# arduino_sheild_1.net
KiCad netlist of a schematic drawn in Altium Designer
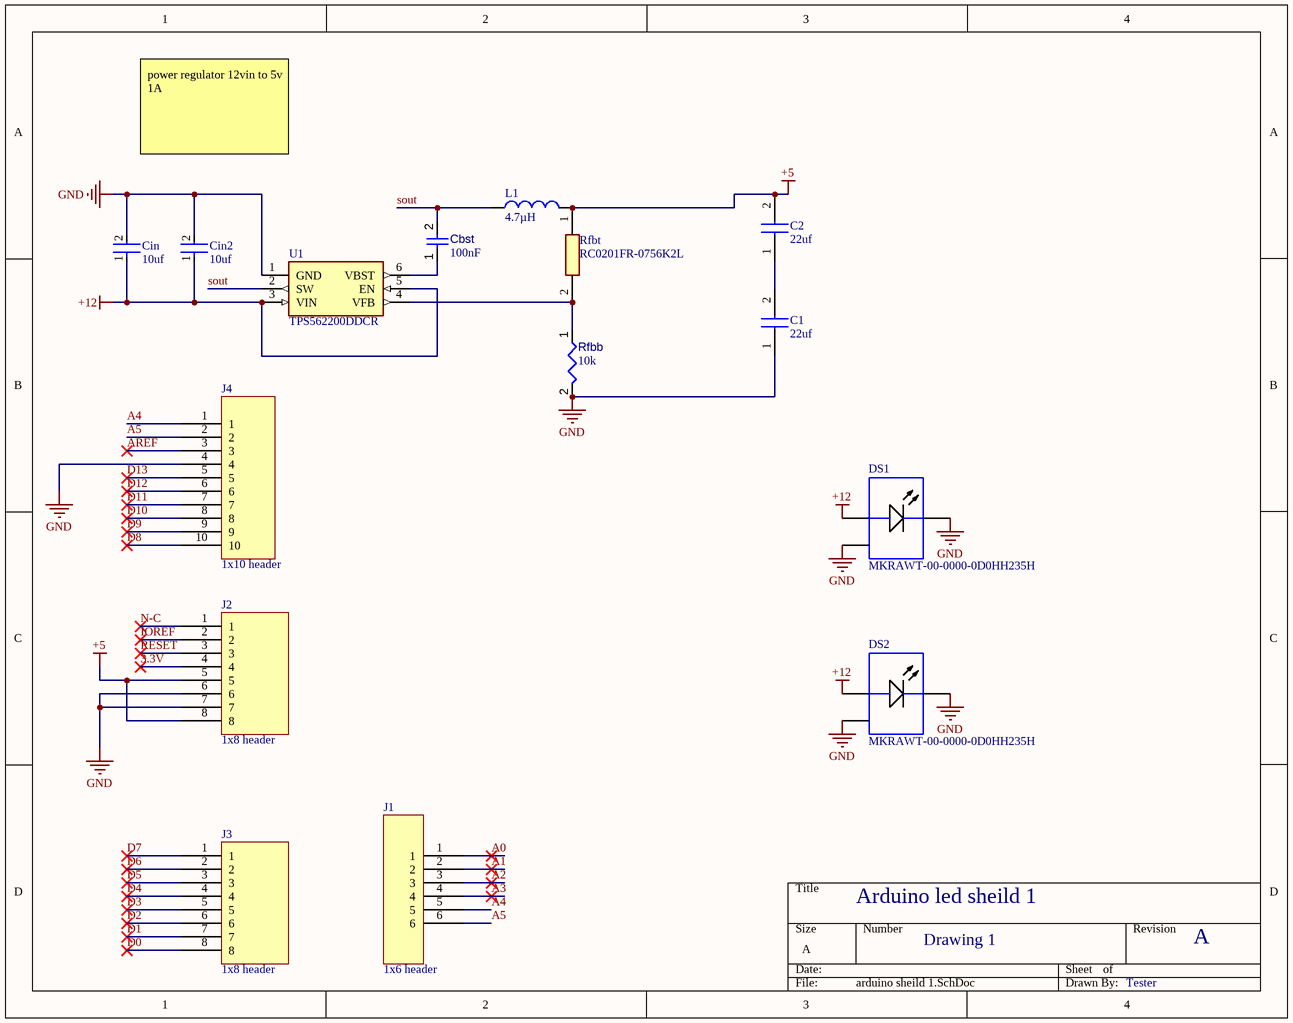
[diagram p0: arduino sheild 1.SchDoc]

(export (version "E")
  (design (tool "Eeschema 10.0.6"))
  (components
    (comp (ref "C1")
      (value "22uf")
      (footprint "SamacSys:CAPC2114X95N")
      (description "Capacitor")
      (fields (field (name "MANUFACTURER_PART_NUMBER") "MSASL219LB5226MTNA01"))
      (libsource (lib "SamacSys") (part "MSASL219LB5226MTNA01"))
    )
    (comp (ref "C2")
      (value "22uf")
      (footprint "SamacSys:CAPC2114X95N")
      (description "Capacitor")
      (fields (field (name "MANUFACTURER_PART_NUMBER") "MSASL219LB5226MTNA01"))
      (libsource (lib "SamacSys") (part "MSASL219LB5226MTNA01"))
    )
    (comp (ref "Cbst")
      (value "100nF")
      (footprint "CAPC2012X75N")
      (description "25V 100nF X7R 卤10% 0805 Multilayer Ceramic Capacitors MLCC - SMD/SMT ROHS")
      (fields (field (name "TOLERANCE") "10%") (field (name "Comment") "08053C104KAT2A"))
      (libsource (lib "Yishak Kalu") (part "CAP-NP-2"))
    )
    (comp (ref "Cin")
      (value "10uf")
      (footprint "FP-GRM21B-0_15-IPC_C")
      (description "Chip Multilayer Ceramic Capacitors for General Purpose, 0805, 10uF, X5R, 15%, 10%, 25V")
      (fields (field (name "VOLTAGE") "25V") (field (name "TOLERANCE") "10%"))
      (libsource (lib "Altium Content Vault") (part "b4654b650e69147ec39a6b967a45e02"))
    )
    (comp (ref "Cin2")
      (value "10uf")
      (footprint "FP-GRM21B-0_15-IPC_C")
      (description "Chip Multilayer Ceramic Capacitors for General Purpose, 0805, 10uF, X5R, 15%, 10%, 25V")
      (fields (field (name "VOLTAGE") "25V") (field (name "TOLERANCE") "10%"))
      (libsource (lib "Altium Content Vault") (part "b4654b650e69147ec39a6b967a45e02"))
    )
    (comp (ref "DS1")
      (value "MKRAWT-00-0000-0D0HH235H")
      (footprint "CREE-MK-R-2_V")
      (description "LED, White, 12 V, 2-Pin SMD, RoHS, Tape and Reel")
      (libsource (lib "Altium Content Vault") (part "LED_WHITE-3"))
    )
    (comp (ref "DS2")
      (value "MKRAWT-00-0000-0D0HH235H")
      (footprint "CREE-MK-R-2_V")
      (description "LED, White, 12 V, 2-Pin SMD, RoHS, Tape and Reel")
      (libsource (lib "Altium Content Vault") (part "LED_WHITE-3"))
    )
    (comp (ref "J1")
      (value "1x6 header")
      (footprint "1x6 header")
      (description "1x6 pin header")
      (libsource (lib "Schlib1") (part "6 pin header"))
    )
    (comp (ref "J2")
      (value "1x8 header")
      (footprint "1x8 header")
      (description "1x8 header pin")
      (libsource (lib "Schlib1") (part "8 pin header"))
    )
    (comp (ref "J3")
      (value "1x8 header")
      (footprint "1x8 header")
      (description "1x8 header pin")
      (libsource (lib "Schlib1") (part "8 pin header"))
    )
    (comp (ref "J4")
      (value "1x10 header")
      (footprint "1x10 pin header")
      (description "1x10 header pin")
      (libsource (lib "Schlib1") (part "10 pin header"))
    )
    (comp (ref "L1")
      (value "4.7µH")
      (footprint "INDP6060X450N")
      (description "Inductor Power Semi-Shielded Wirewound 4.7uH 30% 100KHz 15Q-Factor Ferrite 3A 0.0376Ohm DCR T/R")
      (fields (field (name "TOLERANCE") "30%") (field (name "Comment") "SRN6045-4R7Y"))
      (libsource (lib "Yishak Kalu") (part "IND-2"))
    )
    (comp (ref "Rfbb")
      (value "10k")
      (footprint "RESC0603X26N")
      (description "Res Thick Film 0201 10K Ohm 1% 0.05W(1/20W) ±200ppm/C Pad SMD T/R")
      (fields (field (name "TOLERANCE") "1%") (field (name "Comment") "RC0201FR-0710KL"))
      (libsource (lib "Yishak Kalu") (part "RES-2"))
    )
    (comp (ref "Rfbt")
      (value "RC0201FR-0756K2L")
      (footprint "SamacSys:RESC0603X26N")
      (description "Resistor")
      (fields (field (name "MOUSER PART NUMBER") "603-RC0201FR-0756K2L"))
      (libsource (lib "SamacSys") (part "RC0201FR-0756K2L"))
    )
    (comp (ref "U1")
      (value "TPS562200DDCR")
      (footprint "SamacSys:SOT95P280X110-6N")
      (description "Undefined or Miscellaneous")
      (fields (field (name "MOUSER PART NUMBER") "595-TPS562200DDCR"))
      (libsource (lib "SamacSys") (part "TPS562200DDCR"))
    )
  )
  (nets
    (net (code "1") (name "+5") (class "Default")
      (node (ref "C2") (pin "2") (pinfunction "2_2") (pintype "passive"))
      (node (ref "J2") (pin "5") (pinfunction "5_5") (pintype "passive"))
      (node (ref "J2") (pin "8") (pinfunction "8_8") (pintype "passive"))
      (node (ref "L1") (pin "2") (pinfunction "2_2") (pintype "passive"))
      (node (ref "Rfbt") (pin "1") (pinfunction "1_1") (pintype "passive"))
    )
    (net (code "2") (name "+12") (class "Default")
      (node (ref "Cin") (pin "1") (pinfunction "1_1") (pintype "passive"))
      (node (ref "Cin2") (pin "1") (pinfunction "1_1") (pintype "passive"))
      (node (ref "DS1") (pin "1") (pinfunction "A_1") (pintype "passive"))
      (node (ref "DS2") (pin "1") (pinfunction "A_1") (pintype "passive"))
      (node (ref "U1") (pin "3") (pinfunction "VIN_3") (pintype "input"))
      (node (ref "U1") (pin "5") (pinfunction "EN_5") (pintype "input"))
    )
    (net (code "3") (name "/3.3V") (class "Default")
      (node (ref "J2") (pin "4") (pinfunction "4_4") (pintype "passive+no_connect"))
    )
    (net (code "8") (name "/A0") (class "Default")
      (node (ref "J1") (pin "1") (pinfunction "1_1") (pintype "passive"))
    )
    (net (code "9") (name "/A1") (class "Default")
      (node (ref "J1") (pin "2") (pinfunction "2_2") (pintype "passive"))
    )
    (net (code "10") (name "/A2") (class "Default")
      (node (ref "J1") (pin "3") (pinfunction "3_3") (pintype "passive"))
    )
    (net (code "11") (name "/A3") (class "Default")
      (node (ref "J1") (pin "4") (pinfunction "4_4") (pintype "passive"))
    )
    (net (code "12") (name "/A4") (class "Default")
      (node (ref "J1") (pin "5") (pinfunction "5_5") (pintype "passive"))
      (node (ref "J4") (pin "1") (pinfunction "1_1") (pintype "passive"))
    )
    (net (code "13") (name "/A5") (class "Default")
      (node (ref "J1") (pin "6") (pinfunction "6_6") (pintype "passive"))
      (node (ref "J4") (pin "2") (pinfunction "2_2") (pintype "passive"))
    )
    (net (code "14") (name "/AREF") (class "Default")
      (node (ref "J4") (pin "3") (pinfunction "3_3") (pintype "passive+no_connect"))
    )
    (net (code "15") (name "/D0") (class "Default")
      (node (ref "J3") (pin "8") (pinfunction "8_8") (pintype "passive+no_connect"))
    )
    (net (code "16") (name "/D1") (class "Default")
      (node (ref "J3") (pin "7") (pinfunction "7_7") (pintype "passive+no_connect"))
    )
    (net (code "17") (name "/D2") (class "Default")
      (node (ref "J3") (pin "6") (pinfunction "6_6") (pintype "passive+no_connect"))
    )
    (net (code "18") (name "/D3") (class "Default")
      (node (ref "J3") (pin "5") (pinfunction "5_5") (pintype "passive+no_connect"))
    )
    (net (code "19") (name "/D4") (class "Default")
      (node (ref "J3") (pin "4") (pinfunction "4_4") (pintype "passive+no_connect"))
    )
    (net (code "20") (name "/D5") (class "Default")
      (node (ref "J3") (pin "3") (pinfunction "3_3") (pintype "passive+no_connect"))
    )
    (net (code "21") (name "/D6") (class "Default")
      (node (ref "J3") (pin "2") (pinfunction "2_2") (pintype "passive+no_connect"))
    )
    (net (code "22") (name "/D7") (class "Default")
      (node (ref "J3") (pin "1") (pinfunction "1_1") (pintype "passive+no_connect"))
    )
    (net (code "23") (name "/D8") (class "Default")
      (node (ref "J4") (pin "10") (pinfunction "10_10") (pintype "passive+no_connect"))
    )
    (net (code "24") (name "/D9") (class "Default")
      (node (ref "J4") (pin "9") (pinfunction "9_9") (pintype "passive+no_connect"))
    )
    (net (code "25") (name "/D10") (class "Default")
      (node (ref "J4") (pin "8") (pinfunction "8_8") (pintype "passive+no_connect"))
    )
    (net (code "26") (name "/D11") (class "Default")
      (node (ref "J4") (pin "7") (pinfunction "7_7") (pintype "passive+no_connect"))
    )
    (net (code "27") (name "/D12") (class "Default")
      (node (ref "J4") (pin "6") (pinfunction "6_6") (pintype "passive+no_connect"))
    )
    (net (code "28") (name "/D13") (class "Default")
      (node (ref "J4") (pin "5") (pinfunction "5_5") (pintype "passive+no_connect"))
    )
    (net (code "29") (name "/IOREF") (class "Default")
      (node (ref "J2") (pin "2") (pinfunction "2_2") (pintype "passive+no_connect"))
    )
    (net (code "30") (name "/N-C") (class "Default")
      (node (ref "J2") (pin "1") (pinfunction "1_1") (pintype "passive+no_connect"))
    )
    (net (code "31") (name "/RESET") (class "Default")
      (node (ref "J2") (pin "3") (pinfunction "3_3") (pintype "passive+no_connect"))
    )
    (net (code "32") (name "/sout") (class "Default")
      (node (ref "Cbst") (pin "2") (pinfunction "2_2") (pintype "passive"))
      (node (ref "L1") (pin "1") (pinfunction "1_1") (pintype "passive"))
      (node (ref "U1") (pin "2") (pinfunction "SW_2") (pintype "output"))
    )
    (net (code "33") (name "GND") (class "Default")
      (node (ref "C1") (pin "1") (pinfunction "1_1") (pintype "passive"))
      (node (ref "Cin") (pin "2") (pinfunction "2_2") (pintype "passive"))
      (node (ref "Cin2") (pin "2") (pinfunction "2_2") (pintype "passive"))
      (node (ref "DS1") (pin "2") (pinfunction "K_2") (pintype "passive"))
      (node (ref "DS1") (pin "3") (pinfunction "EP_3") (pintype "passive"))
      (node (ref "DS2") (pin "2") (pinfunction "K_2") (pintype "passive"))
      (node (ref "DS2") (pin "3") (pinfunction "EP_3") (pintype "passive"))
      (node (ref "J2") (pin "6") (pinfunction "6_6") (pintype "passive"))
      (node (ref "J2") (pin "7") (pinfunction "7_7") (pintype "passive"))
      (node (ref "J4") (pin "4") (pinfunction "4_4") (pintype "passive"))
      (node (ref "Rfbb") (pin "2") (pinfunction "2_2") (pintype "passive"))
      (node (ref "U1") (pin "1") (pinfunction "GND_1") (pintype "power_in"))
    )
    (net (code "34") (name "Net-(C1-Pad2)") (class "Default")
      (node (ref "C1") (pin "2") (pinfunction "2_2") (pintype "passive"))
      (node (ref "C2") (pin "1") (pinfunction "1_1") (pintype "passive"))
    )
    (net (code "35") (name "Net-(U1-VBST)") (class "Default")
      (node (ref "Cbst") (pin "1") (pinfunction "1_1") (pintype "passive"))
      (node (ref "U1") (pin "6") (pinfunction "VBST_6") (pintype "output"))
    )
    (net (code "36") (name "Net-(U1-VFB)") (class "Default")
      (node (ref "Rfbb") (pin "1") (pinfunction "1_1") (pintype "passive"))
      (node (ref "Rfbt") (pin "2") (pinfunction "2_2") (pintype "passive"))
      (node (ref "U1") (pin "4") (pinfunction "VFB_4") (pintype "output"))
    )
  )
)
